# Loconet-QuadOD.net
KiCad netlist of a schematic drawn in EAGLE
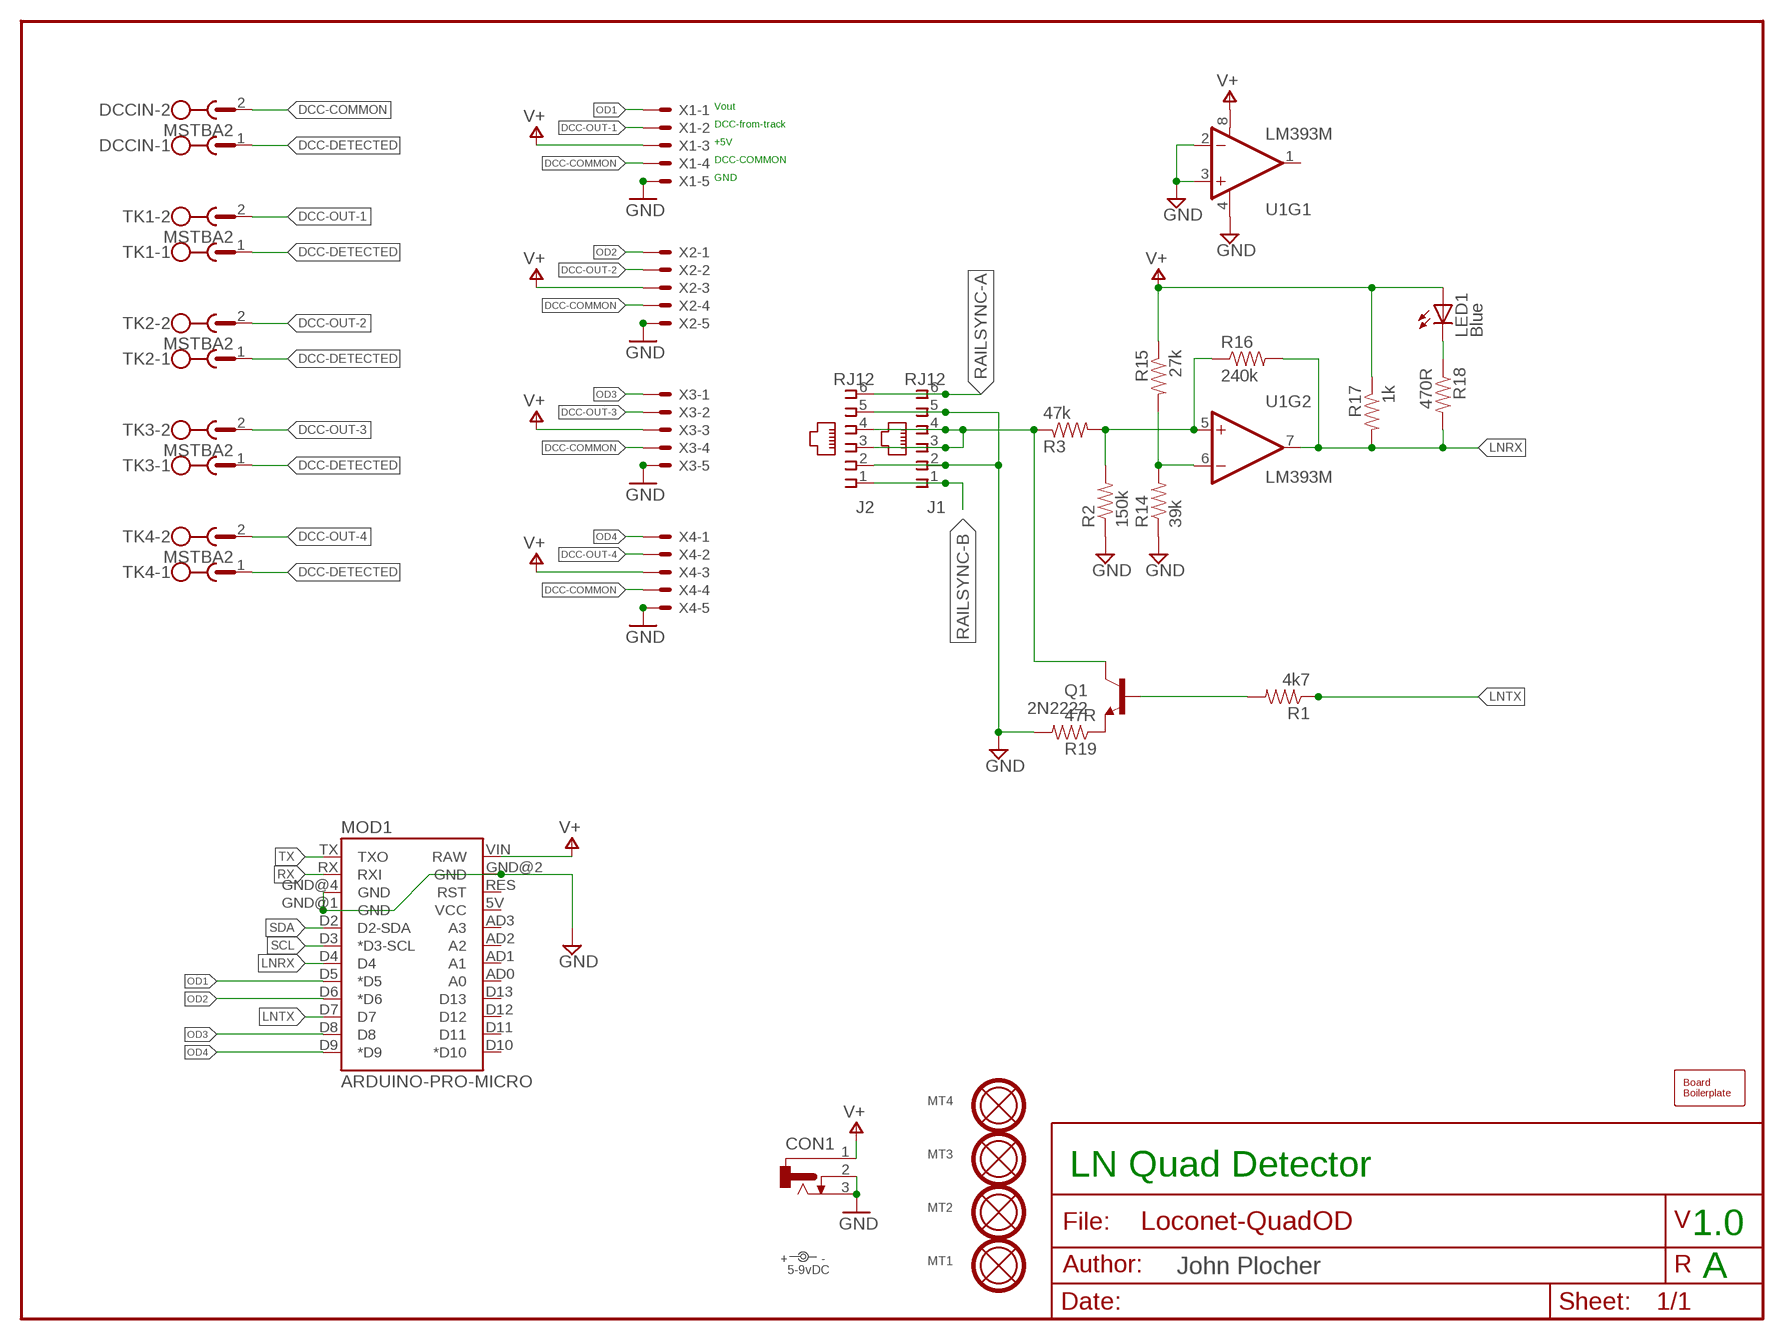
[diagram p0: schematic, sheet 1]

(export (version "E")
  (design (tool "Eeschema 10.0.6"))
  (components
    (comp (ref "BOARD1")
      (value "BOARD100X100-NOHOLES")
      (footprint "eagle-import:BOARD-SEEED10X10-NOHOLES")
      (libsource (lib "eagle-import") (part "BOARD100X100-NOHOLES"))
    )
    (comp (ref "CON1")
      (value "CONNECTOR-DC-POWER-RA")
      (footprint "eagle-import:DCJ0202")
      (libsource (lib "eagle-import") (part "CONNECTOR-DC-POWER-RA"))
    )
    (comp (ref "DCCIN")
      (value "MSTBA2")
      (footprint "eagle-import:MSTBA2")
      (fields (field (name "MF") "FARNELL") (field (name "MPN") "1757242"))
      (libsource (lib "eagle-import") (part "CONNECTOR-MSTBA2-ORIG"))
    )
    (comp (ref "J1")
      (value "RJ12")
      (footprint "eagle-import:RJ25")
      (libsource (lib "eagle-import") (part "CONNECTOR-RJ25CORCOM"))
    )
    (comp (ref "J2")
      (value "RJ12")
      (footprint "eagle-import:RJ25")
      (libsource (lib "eagle-import") (part "CONNECTOR-RJ25CORCOM"))
    )
    (comp (ref "LED1")
      (value "Blue")
      (footprint "eagle-import:0805-LED")
      (libsource (lib "eagle-import") (part "LED0805-LED"))
    )
    (comp (ref "MOD1")
      (value "ARDUINO-PRO-MICRO")
      (footprint "eagle-import:ARDUINO-PRO-MICRO-NOSILK")
      (libsource (lib "eagle-import") (part "ARDUINO-PRO-MICRO"))
    )
    (comp (ref "MT1")
      (value "MOUNTINGHOLE")
      (footprint "eagle-import:MOUNTINGHOLE")
      (libsource (lib "eagle-import") (part "MOUNTINGHOLE"))
    )
    (comp (ref "MT2")
      (value "MOUNTINGHOLE")
      (footprint "eagle-import:MOUNTINGHOLE")
      (libsource (lib "eagle-import") (part "MOUNTINGHOLE"))
    )
    (comp (ref "MT3")
      (value "MOUNTINGHOLE")
      (footprint "eagle-import:MOUNTINGHOLE")
      (libsource (lib "eagle-import") (part "MOUNTINGHOLE"))
    )
    (comp (ref "MT4")
      (value "MOUNTINGHOLE")
      (footprint "eagle-import:MOUNTINGHOLE")
      (libsource (lib "eagle-import") (part "MOUNTINGHOLE"))
    )
    (comp (ref "Q1")
      (value "2N2222")
      (footprint "eagle-import:SOT23")
      (libsource (lib "eagle-import") (part "NPN-SOT23"))
    )
    (comp (ref "R1")
      (value "4k7")
      (footprint "eagle-import:0805-RES")
      (libsource (lib "eagle-import") (part "R0805-RES"))
    )
    (comp (ref "R2")
      (value "150k")
      (footprint "eagle-import:0805-RES")
      (libsource (lib "eagle-import") (part "R0805-RES"))
    )
    (comp (ref "R3")
      (value "47k")
      (footprint "eagle-import:0805-RES")
      (libsource (lib "eagle-import") (part "R0805-RES"))
    )
    (comp (ref "R14")
      (value "39k")
      (footprint "eagle-import:0805-RES")
      (libsource (lib "eagle-import") (part "R0805-RES"))
    )
    (comp (ref "R15")
      (value "27k")
      (footprint "eagle-import:0805-RES")
      (libsource (lib "eagle-import") (part "R0805-RES"))
    )
    (comp (ref "R16")
      (value "240k")
      (footprint "eagle-import:0805-RES")
      (libsource (lib "eagle-import") (part "R0805-RES"))
    )
    (comp (ref "R17")
      (value "1k")
      (footprint "eagle-import:0805-RES")
      (libsource (lib "eagle-import") (part "R0805-RES"))
    )
    (comp (ref "R18")
      (value "470R")
      (footprint "eagle-import:0805-RES")
      (libsource (lib "eagle-import") (part "R0805-RES"))
    )
    (comp (ref "R19")
      (value "47R")
      (footprint "eagle-import:0805-RES")
      (libsource (lib "eagle-import") (part "R0805-RES"))
    )
    (comp (ref "TK1")
      (value "MSTBA2")
      (footprint "eagle-import:MSTBA2")
      (fields (field (name "MF") "FARNELL") (field (name "MPN") "1757242"))
      (libsource (lib "eagle-import") (part "CONNECTOR-MSTBA2-ORIG"))
    )
    (comp (ref "TK2")
      (value "MSTBA2")
      (footprint "eagle-import:MSTBA2")
      (fields (field (name "MF") "FARNELL") (field (name "MPN") "1757242"))
      (libsource (lib "eagle-import") (part "CONNECTOR-MSTBA2-ORIG"))
    )
    (comp (ref "TK3")
      (value "MSTBA2")
      (footprint "eagle-import:MSTBA2")
      (fields (field (name "MF") "FARNELL") (field (name "MPN") "1757242"))
      (libsource (lib "eagle-import") (part "CONNECTOR-MSTBA2-ORIG"))
    )
    (comp (ref "TK4")
      (value "MSTBA2")
      (footprint "eagle-import:MSTBA2")
      (fields (field (name "MF") "FARNELL") (field (name "MPN") "1757242"))
      (libsource (lib "eagle-import") (part "CONNECTOR-MSTBA2-ORIG"))
    )
    (comp (ref "U$1")
      (value "5-9vDC")
      (footprint "eagle-import:PWR_LABEL")
      (libsource (lib "eagle-import") (part "DOC-POWER_LABEL"))
    )
    (comp (ref "U1")
      (value "LM393M")
      (footprint "eagle-import:SO08")
      (libsource (lib "eagle-import") (part "LM393M"))
    )
    (comp (ref "X1")
      (value "KK-156-5")
      (footprint "eagle-import:KK-156-5")
      (libsource (lib "eagle-import") (part "KK-156-5"))
    )
    (comp (ref "X2")
      (value "KK-156-5")
      (footprint "eagle-import:KK-156-5")
      (libsource (lib "eagle-import") (part "KK-156-5"))
    )
    (comp (ref "X3")
      (value "KK-156-5")
      (footprint "eagle-import:KK-156-5")
      (libsource (lib "eagle-import") (part "KK-156-5"))
    )
    (comp (ref "X4")
      (value "KK-156-5")
      (footprint "eagle-import:KK-156-5")
      (libsource (lib "eagle-import") (part "KK-156-5"))
    )
  )
  (nets
    (net (code "1") (name "DCC-COMMON") (class "Default")
      (node (ref "DCCIN") (pin "2") (pinfunction "1_2") (pintype "passive"))
      (node (ref "X1") (pin "4") (pinfunction "S_4") (pintype "passive"))
      (node (ref "X2") (pin "4") (pinfunction "S_4") (pintype "passive"))
      (node (ref "X3") (pin "4") (pinfunction "S_4") (pintype "passive"))
      (node (ref "X4") (pin "4") (pinfunction "S_4") (pintype "passive"))
    )
    (net (code "2") (name "DCC-DETECTED") (class "Default")
      (node (ref "DCCIN") (pin "1") (pinfunction "1_1") (pintype "passive"))
      (node (ref "TK1") (pin "1") (pinfunction "1_1") (pintype "passive"))
      (node (ref "TK2") (pin "1") (pinfunction "1_1") (pintype "passive"))
      (node (ref "TK3") (pin "1") (pinfunction "1_1") (pintype "passive"))
      (node (ref "TK4") (pin "1") (pinfunction "1_1") (pintype "passive"))
    )
    (net (code "3") (name "DCC-OUT-1") (class "Default")
      (node (ref "TK1") (pin "2") (pinfunction "1_2") (pintype "passive"))
      (node (ref "X1") (pin "2") (pinfunction "S_2") (pintype "passive"))
    )
    (net (code "4") (name "DCC-OUT-2") (class "Default")
      (node (ref "TK2") (pin "2") (pinfunction "1_2") (pintype "passive"))
      (node (ref "X2") (pin "2") (pinfunction "S_2") (pintype "passive"))
    )
    (net (code "5") (name "DCC-OUT-3") (class "Default")
      (node (ref "TK3") (pin "2") (pinfunction "1_2") (pintype "passive"))
      (node (ref "X3") (pin "2") (pinfunction "S_2") (pintype "passive"))
    )
    (net (code "6") (name "DCC-OUT-4") (class "Default")
      (node (ref "TK4") (pin "2") (pinfunction "1_2") (pintype "passive"))
      (node (ref "X4") (pin "2") (pinfunction "S_2") (pintype "passive"))
    )
    (net (code "7") (name "GND") (class "Default")
      (node (ref "CON1") (pin "2") (pinfunction "2_2") (pintype "passive"))
      (node (ref "CON1") (pin "3") (pinfunction "3_3") (pintype "passive"))
      (node (ref "J1") (pin "2") (pinfunction "2_2") (pintype "passive"))
      (node (ref "J1") (pin "5") (pinfunction "5_5") (pintype "passive"))
      (node (ref "J2") (pin "2") (pinfunction "2_2") (pintype "passive"))
      (node (ref "J2") (pin "5") (pinfunction "5_5") (pintype "passive"))
      (node (ref "MOD1") (pin "GND@1") (pinfunction "GND_GND@1") (pintype "bidirectional"))
      (node (ref "MOD1") (pin "GND@2") (pinfunction "GND_GND@2") (pintype "bidirectional"))
      (node (ref "MOD1") (pin "GND@4") (pinfunction "GND_GND@4") (pintype "bidirectional"))
      (node (ref "R14") (pin "1") (pinfunction "1_1") (pintype "passive"))
      (node (ref "R19") (pin "2") (pinfunction "2_2") (pintype "passive"))
      (node (ref "R2") (pin "1") (pinfunction "1_1") (pintype "passive"))
      (node (ref "U1") (pin "2") (pinfunction "-IN_2") (pintype "input"))
      (node (ref "U1") (pin "3") (pinfunction "+IN_3") (pintype "input"))
      (node (ref "U1") (pin "4") (pinfunction "V-_4") (pintype "power_in"))
      (node (ref "X1") (pin "5") (pinfunction "S_5") (pintype "passive"))
      (node (ref "X2") (pin "5") (pinfunction "S_5") (pintype "passive"))
      (node (ref "X3") (pin "5") (pinfunction "S_5") (pintype "passive"))
      (node (ref "X4") (pin "5") (pinfunction "S_5") (pintype "passive"))
    )
    (net (code "8") (name "LNRX") (class "Default")
      (node (ref "MOD1") (pin "D4") (pinfunction "D4_D4") (pintype "bidirectional"))
      (node (ref "R16") (pin "2") (pinfunction "2_2") (pintype "passive"))
      (node (ref "R17") (pin "2") (pinfunction "2_2") (pintype "passive"))
      (node (ref "R18") (pin "2") (pinfunction "2_2") (pintype "passive"))
      (node (ref "U1") (pin "7") (pinfunction "OUT_7") (pintype "output"))
    )
    (net (code "9") (name "LNTX") (class "Default")
      (node (ref "MOD1") (pin "D7") (pinfunction "D7_D7") (pintype "bidirectional"))
      (node (ref "R1") (pin "1") (pinfunction "1_1") (pintype "passive"))
    )
    (net (code "10") (name "Net-(LED1-PadC)") (class "Default")
      (node (ref "LED1") (pin "C") (pinfunction "C_C") (pintype "passive"))
      (node (ref "R18") (pin "1") (pinfunction "1_1") (pintype "passive"))
    )
    (net (code "11") (name "Net-(Q1-B)") (class "Default")
      (node (ref "Q1") (pin "1") (pinfunction "B_1") (pintype "passive"))
      (node (ref "R1") (pin "2") (pinfunction "2_2") (pintype "passive"))
    )
    (net (code "12") (name "Net-(Q1-C)") (class "Default")
      (node (ref "J1") (pin "3") (pinfunction "3_3") (pintype "passive"))
      (node (ref "J1") (pin "4") (pinfunction "4_4") (pintype "passive"))
      (node (ref "J2") (pin "3") (pinfunction "3_3") (pintype "passive"))
      (node (ref "J2") (pin "4") (pinfunction "4_4") (pintype "passive"))
      (node (ref "Q1") (pin "3") (pinfunction "C_3") (pintype "passive"))
      (node (ref "R3") (pin "1") (pinfunction "1_1") (pintype "passive"))
    )
    (net (code "13") (name "Net-(Q1-E)") (class "Default")
      (node (ref "Q1") (pin "2") (pinfunction "E_2") (pintype "passive"))
      (node (ref "R19") (pin "1") (pinfunction "1_1") (pintype "passive"))
    )
    (net (code "14") (name "Net-(U1B-+IN)") (class "Default")
      (node (ref "R16") (pin "1") (pinfunction "1_1") (pintype "passive"))
      (node (ref "R2") (pin "2") (pinfunction "2_2") (pintype "passive"))
      (node (ref "R3") (pin "2") (pinfunction "2_2") (pintype "passive"))
      (node (ref "U1") (pin "5") (pinfunction "+IN_5") (pintype "input"))
    )
    (net (code "15") (name "Net-(U1B--IN)") (class "Default")
      (node (ref "R14") (pin "2") (pinfunction "2_2") (pintype "passive"))
      (node (ref "R15") (pin "2") (pinfunction "2_2") (pintype "passive"))
      (node (ref "U1") (pin "6") (pinfunction "-IN_6") (pintype "input"))
    )
    (net (code "16") (name "OD1") (class "Default")
      (node (ref "MOD1") (pin "D5") (pinfunction "*D5_D5") (pintype "bidirectional"))
      (node (ref "X1") (pin "1") (pinfunction "S_1") (pintype "passive"))
    )
    (net (code "17") (name "OD2") (class "Default")
      (node (ref "MOD1") (pin "D6") (pinfunction "*D6_D6") (pintype "bidirectional"))
      (node (ref "X2") (pin "1") (pinfunction "S_1") (pintype "passive"))
    )
    (net (code "18") (name "OD3") (class "Default")
      (node (ref "MOD1") (pin "D8") (pinfunction "D8_D8") (pintype "bidirectional"))
      (node (ref "X3") (pin "1") (pinfunction "S_1") (pintype "passive"))
    )
    (net (code "19") (name "OD4") (class "Default")
      (node (ref "MOD1") (pin "D9") (pinfunction "*D9_D9") (pintype "bidirectional"))
      (node (ref "X4") (pin "1") (pinfunction "S_1") (pintype "passive"))
    )
    (net (code "20") (name "RAILSYNC-A") (class "Default")
      (node (ref "J1") (pin "6") (pinfunction "6_6") (pintype "passive"))
      (node (ref "J2") (pin "6") (pinfunction "6_6") (pintype "passive"))
    )
    (net (code "21") (name "RAILSYNC-B") (class "Default")
      (node (ref "J1") (pin "1") (pinfunction "1_1") (pintype "passive"))
      (node (ref "J2") (pin "1") (pinfunction "1_1") (pintype "passive"))
    )
    (net (code "22") (name "RX") (class "Default")
      (node (ref "MOD1") (pin "RX") (pinfunction "RXI_RX") (pintype "bidirectional"))
    )
    (net (code "23") (name "SCL") (class "Default")
      (node (ref "MOD1") (pin "D3") (pinfunction "*D3-SCL_D3") (pintype "bidirectional"))
    )
    (net (code "24") (name "SDA") (class "Default")
      (node (ref "MOD1") (pin "D2") (pinfunction "D2-SDA_D2") (pintype "bidirectional"))
    )
    (net (code "25") (name "TX") (class "Default")
      (node (ref "MOD1") (pin "TX") (pinfunction "TXO_TX") (pintype "bidirectional"))
    )
    (net (code "26") (name "V+") (class "Default")
      (node (ref "CON1") (pin "1") (pinfunction "1_1") (pintype "passive"))
      (node (ref "LED1") (pin "A") (pinfunction "A_A") (pintype "passive"))
      (node (ref "MOD1") (pin "VIN") (pinfunction "RAW_VIN") (pintype "bidirectional"))
      (node (ref "R15") (pin "1") (pinfunction "1_1") (pintype "passive"))
      (node (ref "R17") (pin "1") (pinfunction "1_1") (pintype "passive"))
      (node (ref "U1") (pin "8") (pinfunction "V+_8") (pintype "power_in"))
      (node (ref "X1") (pin "3") (pinfunction "S_3") (pintype "passive"))
      (node (ref "X2") (pin "3") (pinfunction "S_3") (pintype "passive"))
      (node (ref "X3") (pin "3") (pinfunction "S_3") (pintype "passive"))
      (node (ref "X4") (pin "3") (pinfunction "S_3") (pintype "passive"))
    )
    (net (code "27") (name "unconnected-(MOD1-*D10-PadD10)") (class "Default")
      (node (ref "MOD1") (pin "D10") (pinfunction "*D10_D10") (pintype "bidirectional"))
    )
    (net (code "28") (name "unconnected-(MOD1-A0-PadAD0)") (class "Default")
      (node (ref "MOD1") (pin "AD0") (pinfunction "A0_AD0") (pintype "bidirectional"))
    )
    (net (code "29") (name "unconnected-(MOD1-A1-PadAD1)") (class "Default")
      (node (ref "MOD1") (pin "AD1") (pinfunction "A1_AD1") (pintype "bidirectional"))
    )
    (net (code "30") (name "unconnected-(MOD1-A2-PadAD2)") (class "Default")
      (node (ref "MOD1") (pin "AD2") (pinfunction "A2_AD2") (pintype "bidirectional"))
    )
    (net (code "31") (name "unconnected-(MOD1-A3-PadAD3)") (class "Default")
      (node (ref "MOD1") (pin "AD3") (pinfunction "A3_AD3") (pintype "bidirectional"))
    )
    (net (code "32") (name "unconnected-(MOD1-PadD11)") (class "Default")
      (node (ref "MOD1") (pin "D11") (pinfunction "D11_D11") (pintype "bidirectional"))
    )
    (net (code "33") (name "unconnected-(MOD1-PadD12)") (class "Default")
      (node (ref "MOD1") (pin "D12") (pinfunction "D12_D12") (pintype "bidirectional"))
    )
    (net (code "34") (name "unconnected-(MOD1-PadD13)") (class "Default")
      (node (ref "MOD1") (pin "D13") (pinfunction "D13_D13") (pintype "bidirectional"))
    )
    (net (code "35") (name "unconnected-(MOD1-RST-PadRES)") (class "Default")
      (node (ref "MOD1") (pin "RES") (pinfunction "RST_RES") (pintype "bidirectional"))
    )
    (net (code "36") (name "unconnected-(MOD1-VCC-Pad5V)") (class "Default")
      (node (ref "MOD1") (pin "5V") (pinfunction "VCC_5V") (pintype "bidirectional"))
    )
    (net (code "37") (name "unconnected-(U1A-OUT-Pad1)") (class "Default")
      (node (ref "U1") (pin "1") (pinfunction "OUT_1") (pintype "output"))
    )
  )
)
